# STM32_Lvl-Shft_MCU.net
KiCad netlist of a schematic drawn in Altium Designer
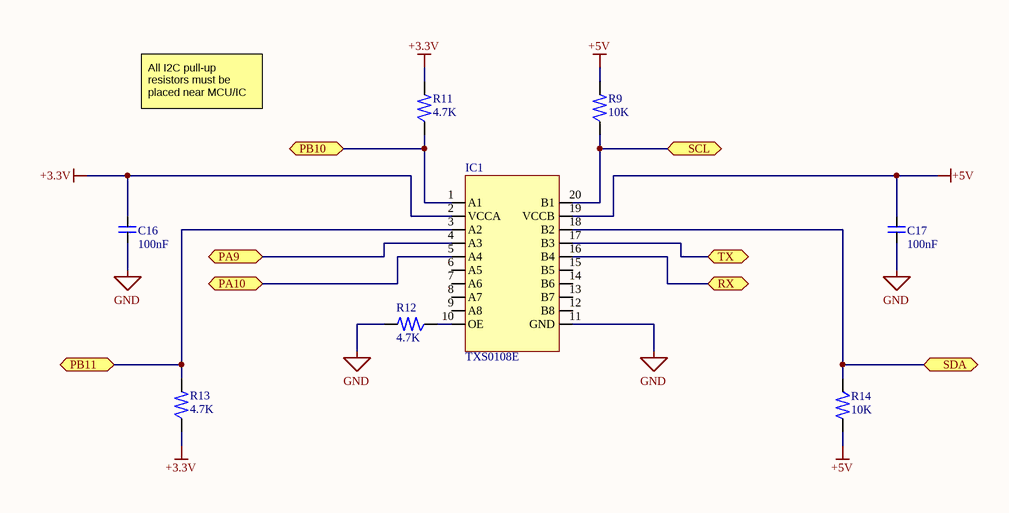
[diagram p0: STM32_Lvl-Shft_MCU.SchDoc]

(export (version "E")
  (design (tool "Eeschema 10.0.6"))
  (components
    (comp (ref "C16")
      (value "100nF")
      (footprint "SMT_CAP_MODEL_1206(3216)_SAMSUNG")
      (description "SMT Samsung Ceramic Capacitor MODEL *V *nF 1206(3216)  CL31B104KBCNNNC(etc.)")
      (libsource (lib "SMT_CAP_MODEL_1206(3216)_SAMSUNG") (part "SMT_CAP_MODEL_1206(3216)_SAMSUNG"))
    )
    (comp (ref "C17")
      (value "100nF")
      (footprint "SMT_CAP_MODEL_1206(3216)_SAMSUNG")
      (description "SMT Samsung Ceramic Capacitor MODEL *V *nF 1206(3216)  CL31B104KBCNNNC(etc.)")
      (libsource (lib "SMT_CAP_MODEL_1206(3216)_SAMSUNG") (part "SMT_CAP_MODEL_1206(3216)_SAMSUNG"))
    )
    (comp (ref "IC1")
      (value "TXS0108E")
      (footprint "SMT_TXS0108E_IC")
      (description "TXS0108E 8-BIT Bi-Directional Level Shifter 1.2-3.6V(A) 1.65-5.5V(B)")
      (libsource (lib "SMT_TXS0108E_IC") (part "SMT_TXS0108E_IC"))
    )
    (comp (ref "R9")
      (value "10K")
      (footprint "SMT_RES_MODEL_1206(3216)_ROHM")
      (description "SMT ROHM Resistor MODEL 1206(3216) 1/4W MCR18ERTJ000")
      (libsource (lib "SMT_RES_MODEL_1206(3216)_ROHM") (part "SMT_RES_MODEL_1206(3216)_ROHM"))
    )
    (comp (ref "R11")
      (value "4.7K")
      (footprint "SMT_RES_MODEL_1206(3216)_ROHM")
      (description "SMT ROHM Resistor MODEL 1206(3216) 1/4W MCR18ERTJ000")
      (libsource (lib "SMT_RES_MODEL_1206(3216)_ROHM") (part "SMT_RES_MODEL_1206(3216)_ROHM"))
    )
    (comp (ref "R12")
      (value "4.7K")
      (footprint "SMT_RES_MODEL_1206(3216)_ROHM")
      (description "SMT ROHM Resistor MODEL 1206(3216) 1/4W MCR18ERTJ000")
      (libsource (lib "SMT_RES_MODEL_1206(3216)_ROHM") (part "SMT_RES_MODEL_1206(3216)_ROHM"))
    )
    (comp (ref "R13")
      (value "4.7K")
      (footprint "SMT_RES_MODEL_1206(3216)_ROHM")
      (description "SMT ROHM Resistor MODEL 1206(3216) 1/4W MCR18ERTJ000")
      (libsource (lib "SMT_RES_MODEL_1206(3216)_ROHM") (part "SMT_RES_MODEL_1206(3216)_ROHM"))
    )
    (comp (ref "R14")
      (value "10K")
      (footprint "SMT_RES_MODEL_1206(3216)_ROHM")
      (description "SMT ROHM Resistor MODEL 1206(3216) 1/4W MCR18ERTJ000")
      (libsource (lib "SMT_RES_MODEL_1206(3216)_ROHM") (part "SMT_RES_MODEL_1206(3216)_ROHM"))
    )
  )
  (nets
    (net (code "1") (name "+3.3V") (class "Default")
      (node (ref "C16") (pin "1") (pinfunction "1_1") (pintype "passive"))
      (node (ref "IC1") (pin "2") (pinfunction "VCCA_2") (pintype "passive"))
      (node (ref "R11") (pin "1") (pinfunction "1_1") (pintype "passive"))
      (node (ref "R13") (pin "2") (pinfunction "2_2") (pintype "passive"))
    )
    (net (code "2") (name "+5V") (class "Default")
      (node (ref "C17") (pin "1") (pinfunction "1_1") (pintype "passive"))
      (node (ref "IC1") (pin "19") (pinfunction "VCCB_19") (pintype "passive"))
      (node (ref "R14") (pin "1") (pinfunction "1_1") (pintype "passive"))
      (node (ref "R9") (pin "1") (pinfunction "1_1") (pintype "passive"))
    )
    (net (code "3") (name "/PA9") (class "Default")
      (node (ref "IC1") (pin "4") (pinfunction "A3_4") (pintype "passive"))
    )
    (net (code "4") (name "/PA10") (class "Default")
      (node (ref "IC1") (pin "5") (pinfunction "A4_5") (pintype "passive"))
    )
    (net (code "5") (name "/PB10") (class "Default")
      (node (ref "IC1") (pin "1") (pinfunction "A1_1") (pintype "passive"))
      (node (ref "R11") (pin "2") (pinfunction "2_2") (pintype "passive"))
    )
    (net (code "6") (name "/PB11") (class "Default")
      (node (ref "IC1") (pin "3") (pinfunction "A2_3") (pintype "passive"))
      (node (ref "R13") (pin "1") (pinfunction "1_1") (pintype "passive"))
    )
    (net (code "7") (name "/RX") (class "Default")
      (node (ref "IC1") (pin "16") (pinfunction "B4_16") (pintype "passive"))
    )
    (net (code "8") (name "/SCL") (class "Default")
      (node (ref "IC1") (pin "20") (pinfunction "B1_20") (pintype "passive"))
      (node (ref "R9") (pin "2") (pinfunction "2_2") (pintype "passive"))
    )
    (net (code "9") (name "/SDA") (class "Default")
      (node (ref "IC1") (pin "18") (pinfunction "B2_18") (pintype "passive"))
      (node (ref "R14") (pin "2") (pinfunction "2_2") (pintype "passive"))
    )
    (net (code "10") (name "/TX") (class "Default")
      (node (ref "IC1") (pin "17") (pinfunction "B3_17") (pintype "passive"))
    )
    (net (code "11") (name "GND") (class "Default")
      (node (ref "C16") (pin "2") (pinfunction "2_2") (pintype "passive"))
      (node (ref "C17") (pin "2") (pinfunction "2_2") (pintype "passive"))
      (node (ref "IC1") (pin "11") (pinfunction "GND_11") (pintype "passive"))
      (node (ref "R12") (pin "1") (pinfunction "1_1") (pintype "passive"))
    )
    (net (code "12") (name "Net-(IC1-OE)") (class "Default")
      (node (ref "IC1") (pin "10") (pinfunction "OE_10") (pintype "passive"))
      (node (ref "R12") (pin "2") (pinfunction "2_2") (pintype "passive"))
    )
    (net (code "13") (name "unconnected-(IC1-A5-Pad6)") (class "Default")
      (node (ref "IC1") (pin "6") (pinfunction "A5_6") (pintype "passive"))
    )
    (net (code "14") (name "unconnected-(IC1-A6-Pad7)") (class "Default")
      (node (ref "IC1") (pin "7") (pinfunction "A6_7") (pintype "passive"))
    )
    (net (code "15") (name "unconnected-(IC1-A7-Pad8)") (class "Default")
      (node (ref "IC1") (pin "8") (pinfunction "A7_8") (pintype "passive"))
    )
    (net (code "16") (name "unconnected-(IC1-A8-Pad9)") (class "Default")
      (node (ref "IC1") (pin "9") (pinfunction "A8_9") (pintype "passive"))
    )
    (net (code "17") (name "unconnected-(IC1-B5-Pad15)") (class "Default")
      (node (ref "IC1") (pin "15") (pinfunction "B5_15") (pintype "passive"))
    )
    (net (code "18") (name "unconnected-(IC1-B6-Pad14)") (class "Default")
      (node (ref "IC1") (pin "14") (pinfunction "B6_14") (pintype "passive"))
    )
    (net (code "19") (name "unconnected-(IC1-B7-Pad13)") (class "Default")
      (node (ref "IC1") (pin "13") (pinfunction "B7_13") (pintype "passive"))
    )
    (net (code "20") (name "unconnected-(IC1-B8-Pad12)") (class "Default")
      (node (ref "IC1") (pin "12") (pinfunction "B8_12") (pintype "passive"))
    )
  )
)
